# isoDebug-FTDI.net
KiCad netlist of a schematic drawn in Altium Designer
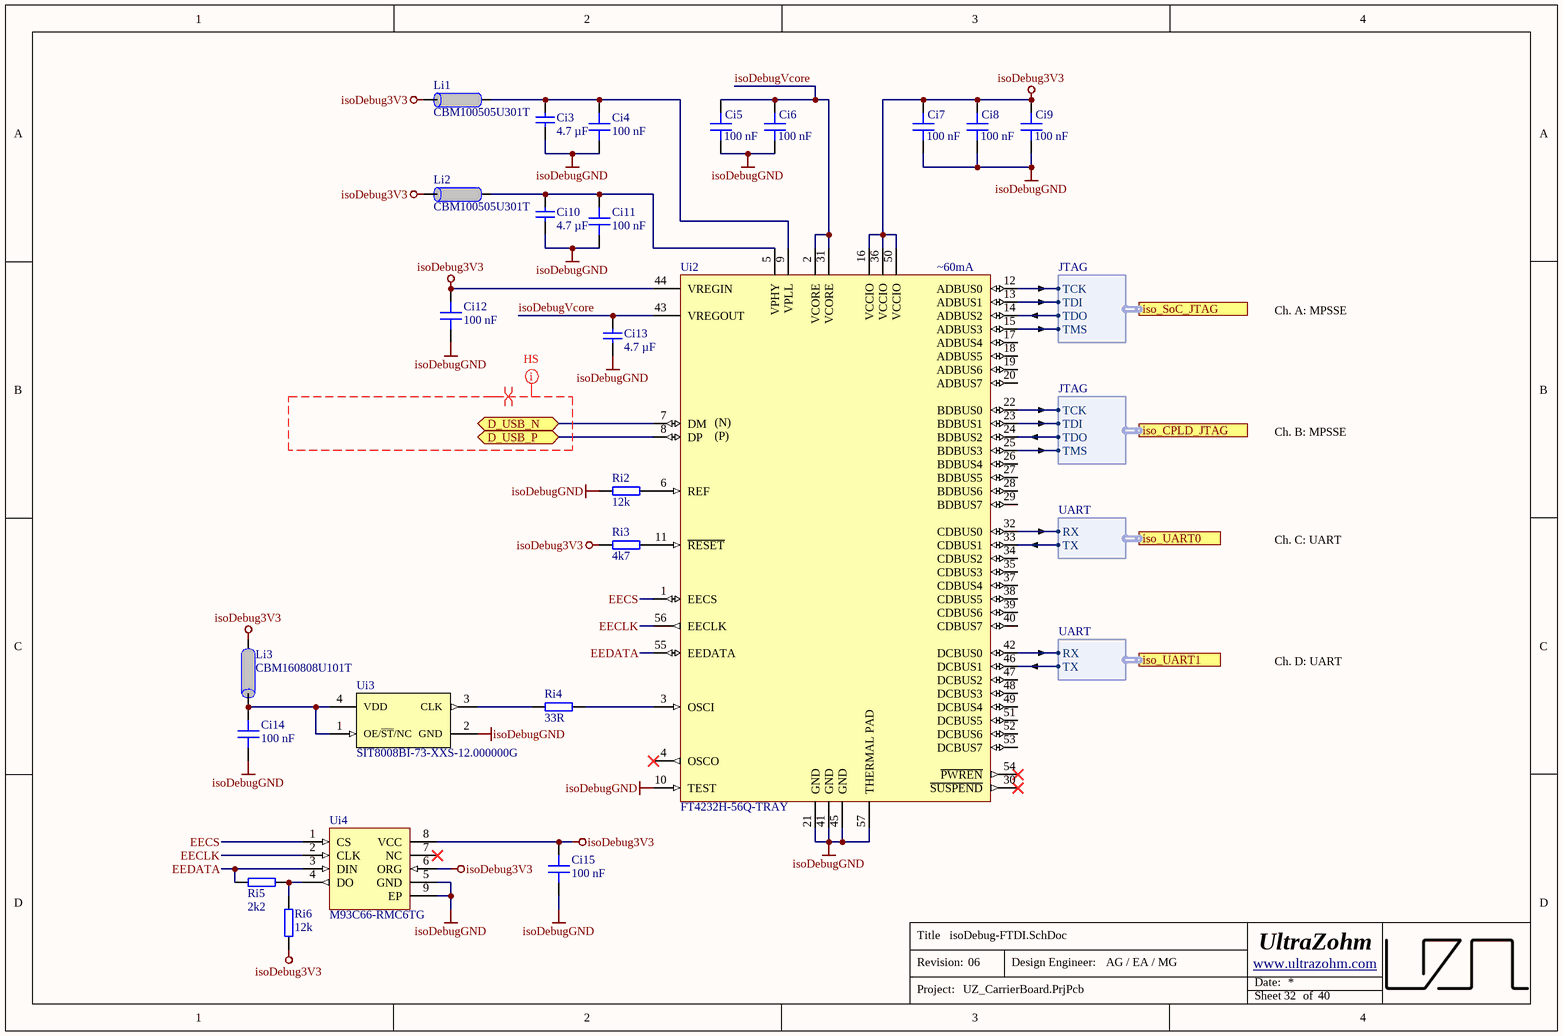
[diagram p0: isoDebug-FTDI.SchDoc]

(export (version "E")
  (design (tool "Eeschema 10.0.6"))
  (components
    (comp (ref "Ci3")
      (value "4.7 µF")
      (footprint "C_0603_TE")
      (description "Generic capacitor")
      (fields
        (field (name "MANUFACTURER PART NUMBER") "UZgen_C_0603_4.7uF_16V_X5R")
        (field (name "MANUFACTURER") "UZgen")
        (field (name "CREATED FROM") "MGeier")
      )
      (libsource (lib "user") (part "CAP-NP"))
    )
    (comp (ref "Ci4")
      (value "100 nF")
      (footprint "C_0402_TE")
      (description "50V 100nF X7R ±10% 0402 Multilayer Ceramic Capacitors MLCC - SMD/SMT ROHS")
      (fields
        (field (name "MANUFACTURER PART NUMBER") "GRM155R71H104KE14D")
        (field (name "MANUFACTURER") "Murata Electronics")
        (field (name "CREATED FROM") "AGeiger")
      )
      (libsource (lib "user") (part "Capacitor"))
    )
    (comp (ref "Ci5")
      (value "100 nF")
      (footprint "C_0402_TE")
      (description "50V 100nF X7R ±10% 0402 Multilayer Ceramic Capacitors MLCC - SMD/SMT ROHS")
      (fields
        (field (name "MANUFACTURER PART NUMBER") "GRM155R71H104KE14D")
        (field (name "MANUFACTURER") "Murata Electronics")
        (field (name "CREATED FROM") "AGeiger")
      )
      (libsource (lib "user") (part "Capacitor"))
    )
    (comp (ref "Ci6")
      (value "100 nF")
      (footprint "C_0402_TE")
      (description "50V 100nF X7R ±10% 0402 Multilayer Ceramic Capacitors MLCC - SMD/SMT ROHS")
      (fields
        (field (name "MANUFACTURER PART NUMBER") "GRM155R71H104KE14D")
        (field (name "MANUFACTURER") "Murata Electronics")
        (field (name "CREATED FROM") "AGeiger")
      )
      (libsource (lib "user") (part "Capacitor"))
    )
    (comp (ref "Ci7")
      (value "100 nF")
      (footprint "C_0402_TE")
      (description "50V 100nF X7R ±10% 0402 Multilayer Ceramic Capacitors MLCC - SMD/SMT ROHS")
      (fields
        (field (name "MANUFACTURER PART NUMBER") "GRM155R71H104KE14D")
        (field (name "MANUFACTURER") "Murata Electronics")
        (field (name "CREATED FROM") "AGeiger")
      )
      (libsource (lib "user") (part "Capacitor"))
    )
    (comp (ref "Ci8")
      (value "100 nF")
      (footprint "C_0402_TE")
      (description "50V 100nF X7R ±10% 0402 Multilayer Ceramic Capacitors MLCC - SMD/SMT ROHS")
      (fields
        (field (name "MANUFACTURER PART NUMBER") "GRM155R71H104KE14D")
        (field (name "MANUFACTURER") "Murata Electronics")
        (field (name "CREATED FROM") "AGeiger")
      )
      (libsource (lib "user") (part "Capacitor"))
    )
    (comp (ref "Ci9")
      (value "100 nF")
      (footprint "C_0402_TE")
      (description "50V 100nF X7R ±10% 0402 Multilayer Ceramic Capacitors MLCC - SMD/SMT ROHS")
      (fields
        (field (name "MANUFACTURER PART NUMBER") "GRM155R71H104KE14D")
        (field (name "MANUFACTURER") "Murata Electronics")
        (field (name "CREATED FROM") "AGeiger")
      )
      (libsource (lib "user") (part "Capacitor"))
    )
    (comp (ref "Ci10")
      (value "4.7 µF")
      (footprint "C_0603_TE")
      (description "Generic capacitor")
      (fields
        (field (name "MANUFACTURER PART NUMBER") "UZgen_C_0603_4.7uF_16V_X5R")
        (field (name "MANUFACTURER") "UZgen")
        (field (name "CREATED FROM") "MGeier")
      )
      (libsource (lib "user") (part "CAP-NP"))
    )
    (comp (ref "Ci11")
      (value "100 nF")
      (footprint "C_0402_TE")
      (description "50V 100nF X7R ±10% 0402 Multilayer Ceramic Capacitors MLCC - SMD/SMT ROHS")
      (fields
        (field (name "MANUFACTURER PART NUMBER") "GRM155R71H104KE14D")
        (field (name "MANUFACTURER") "Murata Electronics")
        (field (name "CREATED FROM") "AGeiger")
      )
      (libsource (lib "user") (part "Capacitor"))
    )
    (comp (ref "Ci12")
      (value "100 nF")
      (footprint "C_0402_TE")
      (description "50V 100nF X7R ±10% 0402 Multilayer Ceramic Capacitors MLCC - SMD/SMT ROHS")
      (fields
        (field (name "MANUFACTURER PART NUMBER") "GRM155R71H104KE14D")
        (field (name "MANUFACTURER") "Murata Electronics")
        (field (name "CREATED FROM") "AGeiger")
      )
      (libsource (lib "user") (part "Capacitor"))
    )
    (comp (ref "Ci13")
      (value "4.7 µF")
      (footprint "C_0603_TE")
      (description "Generic capacitor")
      (fields
        (field (name "MANUFACTURER PART NUMBER") "UZgen_C_0603_4.7uF_16V_X5R")
        (field (name "MANUFACTURER") "UZgen")
        (field (name "CREATED FROM") "MGeier")
      )
      (libsource (lib "user") (part "CAP-NP"))
    )
    (comp (ref "Ci14")
      (value "100 nF")
      (footprint "C_0402_TE")
      (description "50V 100nF X7R ±10% 0402 Multilayer Ceramic Capacitors MLCC - SMD/SMT ROHS")
      (fields
        (field (name "MANUFACTURER PART NUMBER") "GRM155R71H104KE14D")
        (field (name "MANUFACTURER") "Murata Electronics")
        (field (name "CREATED FROM") "AGeiger")
      )
      (libsource (lib "user") (part "Capacitor"))
    )
    (comp (ref "Ci15")
      (value "100 nF")
      (footprint "C_0402_TE")
      (description "50V 100nF X7R ±10% 0402 Multilayer Ceramic Capacitors MLCC - SMD/SMT ROHS")
      (fields
        (field (name "MANUFACTURER PART NUMBER") "GRM155R71H104KE14D")
        (field (name "MANUFACTURER") "Murata Electronics")
        (field (name "CREATED FROM") "AGeiger")
      )
      (libsource (lib "user") (part "Capacitor"))
    )
    (comp (ref "Li1")
      (value "CBM100505U301T")
      (footprint "IND_0402_TE")
      (description "300mΩ ±25% 300Ω@100MHz 0402 Ferrite Beads ROHS")
      (fields
        (field (name "MANUFACTURER") "FH (Guangdong Fenghua Advanced Tech)")
        (field (name "LCSC PART NUMBER") "C394406")
        (field (name "CREATED FROM") "AGeiger")
      )
      (libsource (lib "user") (part "Ferrite_Bead"))
    )
    (comp (ref "Li2")
      (value "CBM100505U301T")
      (footprint "IND_0402_TE")
      (description "300mΩ ±25% 300Ω@100MHz 0402 Ferrite Beads ROHS")
      (fields
        (field (name "MANUFACTURER") "FH (Guangdong Fenghua Advanced Tech)")
        (field (name "LCSC PART NUMBER") "C394406")
        (field (name "CREATED FROM") "AGeiger")
      )
      (libsource (lib "user") (part "Ferrite_Bead"))
    )
    (comp (ref "Li3")
      (value "CBM160808U101T")
      (footprint "IND_0603_TE")
      (description "60mΩ ±25% 100Ω@100MHz 0603 Ferrite Beads ROHS")
      (fields
        (field (name "MANUFACTURER") "FH (Guangdong Fenghua Advanced Tech)")
        (field (name "LCSC PART NUMBER") "C361675")
        (field (name "CREATED FROM") "AGeiger")
      )
      (libsource (lib "") (part "Ferrite_Bead_1"))
    )
    (comp (ref "Ri2")
      (value "12k")
      (footprint "R_0603_TE")
      (description "Generic resistor")
      (fields
        (field (name "MANUFACTURER PART NUMBER") "UZgen_R_0603_12k")
        (field (name "MANUFACTURER") "UZgen")
        (field (name "CREATED FROM") "UZgenTool")
      )
      (libsource (lib "user") (part "RES"))
    )
    (comp (ref "Ri3")
      (value "4k7")
      (footprint "R_0603_TE")
      (description "Generic resistor")
      (fields
        (field (name "MANUFACTURER PART NUMBER") "UZgen_R_0603_4k7")
        (field (name "MANUFACTURER") "UZgen")
        (field (name "CREATED FROM") "UZgenTool")
      )
      (libsource (lib "user") (part "RES"))
    )
    (comp (ref "Ri4")
      (value "33R")
      (footprint "R_0603_TE")
      (description "Generic resistor")
      (fields
        (field (name "MANUFACTURER PART NUMBER") "UZgen_R_0603_33R")
        (field (name "MANUFACTURER") "UZgen")
        (field (name "CREATED FROM") "UZgenTool")
      )
      (libsource (lib "user") (part "RES"))
    )
    (comp (ref "Ri5")
      (value "2k2")
      (footprint "R_0603_TE")
      (description "Generic resistor")
      (fields
        (field (name "MANUFACTURER PART NUMBER") "UZgen_R_0603_2k2")
        (field (name "MANUFACTURER") "UZgen")
        (field (name "CREATED FROM") "UZgenTool")
      )
      (libsource (lib "user") (part "RES"))
    )
    (comp (ref "Ri6")
      (value "12k")
      (footprint "R_0603_TE")
      (description "Generic resistor")
      (fields
        (field (name "MANUFACTURER PART NUMBER") "UZgen_R_0603_12k")
        (field (name "MANUFACTURER") "UZgen")
        (field (name "CREATED FROM") "UZgenTool")
      )
      (libsource (lib "user") (part "RES"))
    )
    (comp (ref "Ui2")
      (value "FT4232H-56Q-TRAY")
      (footprint "QFN50P800X800-57T610X610N")
      (description "USB Interface IC Quad 480Mbs 4 UART USB 2.0 12Mbit")
      (fields
        (field (name "MANUFACTURER") "FTDI")
        (field (name "LCSC PART NUMBER") "C1521561")
        (field (name "CREATED FROM") "AGeiger")
      )
      (libsource (lib "user") (part "FT4232H-56Q"))
    )
    (comp (ref "Ui3")
      (value "SIT8008BI-73-XXS-12.000000G")
      (footprint "2016")
      (description "Clock-Standardoszillatoren -40 to 85C, 2016, 50ppm, 2.25V-3.63V, 12MHz, ST, 250 pcs T&R 8 mm")
      (fields
        (field (name "MANUFACTURER") "SiTime")
        (field (name "LCSC PART NUMBER") "C1508636")
        (field (name "CREATED FROM") "AGeiger")
      )
      (libsource (lib "user") (part "SiT8103"))
    )
    (comp (ref "Ui4")
      (value "M93C66-RMC6TG")
      (footprint "UFDFPN8")
      (description "4Kbit MICROWIRE EE 1.8 V to 5.5 V")
      (fields
        (field (name "MANUFACTURER") "STMicroelectronics")
        (field (name "LCSC PART NUMBER") "C2061956")
        (field (name "CREATED FROM") "AGeiger")
      )
      (libsource (lib "user") (part "M93C46-MN6P"))
    )
  )
  (nets
    (net (code "3") (name "/D_USB_N") (class "Default")
      (node (ref "Ui2") (pin "7") (pinfunction "DM_7") (pintype "bidirectional"))
    )
    (net (code "4") (name "/D_USB_P") (class "Default")
      (node (ref "Ui2") (pin "8") (pinfunction "DP_8") (pintype "bidirectional"))
    )
    (net (code "5") (name "/EECLK") (class "Default")
      (node (ref "Ui2") (pin "56") (pinfunction "EECLK_56") (pintype "output"))
      (node (ref "Ui4") (pin "2") (pinfunction "CLK_2") (pintype "input"))
    )
    (net (code "6") (name "/EECS") (class "Default")
      (node (ref "Ui2") (pin "1") (pinfunction "EECS_1") (pintype "bidirectional"))
      (node (ref "Ui4") (pin "1") (pinfunction "CS_1") (pintype "input"))
    )
    (net (code "7") (name "/EEDATA") (class "Default")
      (node (ref "Ri5") (pin "1") (pinfunction "1_1") (pintype "passive"))
      (node (ref "Ui2") (pin "55") (pinfunction "EEDATA_55") (pintype "bidirectional"))
      (node (ref "Ui4") (pin "3") (pinfunction "DIN_3") (pintype "input"))
    )
    (net (code "8") (name "/isoDebugVcore") (class "Default")
      (node (ref "Ci13") (pin "2") (pinfunction "2_2") (pintype "passive"))
      (node (ref "Ci5") (pin "2") (pinfunction "2_2") (pintype "passive"))
      (node (ref "Ci6") (pin "2") (pinfunction "2_2") (pintype "passive"))
      (node (ref "Ui2") (pin "2") (pinfunction "VCORE_2") (pintype "power_in"))
      (node (ref "Ui2") (pin "31") (pinfunction "VCORE_31") (pintype "power_in"))
      (node (ref "Ui2") (pin "43") (pinfunction "VREGOUT_43") (pintype "power_in"))
    )
    (net (code "11") (name "Net-(Ui2-OSCI)") (class "Default")
      (node (ref "Ri4") (pin "2") (pinfunction "2_2") (pintype "passive"))
      (node (ref "Ui2") (pin "3") (pinfunction "OSCI_3") (pintype "input"))
    )
    (net (code "12") (name "Net-(Ui2-REF)") (class "Default")
      (node (ref "Ri2") (pin "2") (pinfunction "2_2") (pintype "passive"))
      (node (ref "Ui2") (pin "6") (pinfunction "REF_6") (pintype "input"))
    )
    (net (code "13") (name "Net-(Ui2-VPHY)") (class "Default")
      (node (ref "Ci10") (pin "2") (pinfunction "2_2") (pintype "passive"))
      (node (ref "Ci11") (pin "2") (pinfunction "2_2") (pintype "passive"))
      (node (ref "Li2") (pin "1") (pinfunction "1_1") (pintype "passive"))
      (node (ref "Ui2") (pin "5") (pinfunction "VPHY_5") (pintype "power_in"))
    )
    (net (code "14") (name "Net-(Ui2-VPLL)") (class "Default")
      (node (ref "Ci3") (pin "2") (pinfunction "2_2") (pintype "passive"))
      (node (ref "Ci4") (pin "2") (pinfunction "2_2") (pintype "passive"))
      (node (ref "Li1") (pin "1") (pinfunction "1_1") (pintype "passive"))
      (node (ref "Ui2") (pin "9") (pinfunction "VPLL_9") (pintype "power_in"))
    )
    (net (code "15") (name "Net-(Ui2-~{RESET})") (class "Default")
      (node (ref "Ri3") (pin "2") (pinfunction "2_2") (pintype "passive"))
      (node (ref "Ui2") (pin "11") (pinfunction "~{RESET}_11") (pintype "input"))
    )
    (net (code "16") (name "Net-(Ui3-CLK)") (class "Default")
      (node (ref "Ri4") (pin "1") (pinfunction "1_1") (pintype "passive"))
      (node (ref "Ui3") (pin "3") (pinfunction "CLK_3") (pintype "output"))
    )
    (net (code "17") (name "Net-(Ui3-OE{slash}~{ST}{slash}NC)") (class "Default")
      (node (ref "Ci14") (pin "2") (pinfunction "2_2") (pintype "passive"))
      (node (ref "Li3") (pin "2") (pinfunction "2_2") (pintype "passive"))
      (node (ref "Ui3") (pin "1") (pinfunction "OE/~{ST}/NC_1") (pintype "input"))
      (node (ref "Ui3") (pin "4") (pinfunction "VDD_4") (pintype "power_in"))
    )
    (net (code "18") (name "Net-(Ui4-DO)") (class "Default")
      (node (ref "Ri5") (pin "2") (pinfunction "2_2") (pintype "passive"))
      (node (ref "Ri6") (pin "2") (pinfunction "2_2") (pintype "passive"))
      (node (ref "Ui4") (pin "4") (pinfunction "DO_4") (pintype "output"))
    )
    (net (code "19") (name "isoDebug3V3") (class "Default")
      (node (ref "Ci12") (pin "2") (pinfunction "2_2") (pintype "passive"))
      (node (ref "Ci15") (pin "2") (pinfunction "2_2") (pintype "passive"))
      (node (ref "Ci7") (pin "2") (pinfunction "2_2") (pintype "passive"))
      (node (ref "Ci8") (pin "2") (pinfunction "2_2") (pintype "passive"))
      (node (ref "Ci9") (pin "2") (pinfunction "2_2") (pintype "passive"))
      (node (ref "Li1") (pin "2") (pinfunction "2_2") (pintype "passive"))
      (node (ref "Li2") (pin "2") (pinfunction "2_2") (pintype "passive"))
      (node (ref "Li3") (pin "1") (pinfunction "1_1") (pintype "passive"))
      (node (ref "Ri3") (pin "1") (pinfunction "1_1") (pintype "passive"))
      (node (ref "Ri6") (pin "1") (pinfunction "1_1") (pintype "passive"))
      (node (ref "Ui2") (pin "16") (pinfunction "VCCIO_16") (pintype "power_in"))
      (node (ref "Ui2") (pin "36") (pinfunction "VCCIO_36") (pintype "power_in"))
      (node (ref "Ui2") (pin "44") (pinfunction "VREGIN_44") (pintype "power_in"))
      (node (ref "Ui2") (pin "50") (pinfunction "VCCIO_50") (pintype "power_in"))
      (node (ref "Ui4") (pin "6") (pinfunction "ORG_6") (pintype "input"))
      (node (ref "Ui4") (pin "8") (pinfunction "VCC_8") (pintype "power_in"))
    )
    (net (code "20") (name "isoDebugGND") (class "Default")
      (node (ref "Ci10") (pin "1") (pinfunction "1_1") (pintype "passive"))
      (node (ref "Ci11") (pin "1") (pinfunction "1_1") (pintype "passive"))
      (node (ref "Ci12") (pin "1") (pinfunction "1_1") (pintype "passive"))
      (node (ref "Ci13") (pin "1") (pinfunction "1_1") (pintype "passive"))
      (node (ref "Ci14") (pin "1") (pinfunction "1_1") (pintype "passive"))
      (node (ref "Ci15") (pin "1") (pinfunction "1_1") (pintype "passive"))
      (node (ref "Ci3") (pin "1") (pinfunction "1_1") (pintype "passive"))
      (node (ref "Ci4") (pin "1") (pinfunction "1_1") (pintype "passive"))
      (node (ref "Ci5") (pin "1") (pinfunction "1_1") (pintype "passive"))
      (node (ref "Ci6") (pin "1") (pinfunction "1_1") (pintype "passive"))
      (node (ref "Ci7") (pin "1") (pinfunction "1_1") (pintype "passive"))
      (node (ref "Ci8") (pin "1") (pinfunction "1_1") (pintype "passive"))
      (node (ref "Ci9") (pin "1") (pinfunction "1_1") (pintype "passive"))
      (node (ref "Ri2") (pin "1") (pinfunction "1_1") (pintype "passive"))
      (node (ref "Ui2") (pin "10") (pinfunction "TEST_10") (pintype "input"))
      (node (ref "Ui2") (pin "21") (pinfunction "GND_21") (pintype "power_in"))
      (node (ref "Ui2") (pin "41") (pinfunction "GND_41") (pintype "power_in"))
      (node (ref "Ui2") (pin "45") (pinfunction "GND_45") (pintype "power_in"))
      (node (ref "Ui2") (pin "57") (pinfunction "THERMAL_PAD_57") (pintype "power_in"))
      (node (ref "Ui3") (pin "2") (pinfunction "GND_2") (pintype "power_in"))
      (node (ref "Ui4") (pin "5") (pinfunction "GND_5") (pintype "power_in"))
      (node (ref "Ui4") (pin "9") (pinfunction "EP_9") (pintype "power_in"))
    )
    (net (code "21") (name "unconnected-(Ui2-ADBUS0-Pad12)") (class "Default")
      (node (ref "Ui2") (pin "12") (pinfunction "ADBUS0_12") (pintype "bidirectional"))
    )
    (net (code "22") (name "unconnected-(Ui2-ADBUS1-Pad13)") (class "Default")
      (node (ref "Ui2") (pin "13") (pinfunction "ADBUS1_13") (pintype "bidirectional"))
    )
    (net (code "23") (name "unconnected-(Ui2-ADBUS2-Pad14)") (class "Default")
      (node (ref "Ui2") (pin "14") (pinfunction "ADBUS2_14") (pintype "bidirectional"))
    )
    (net (code "24") (name "unconnected-(Ui2-ADBUS3-Pad15)") (class "Default")
      (node (ref "Ui2") (pin "15") (pinfunction "ADBUS3_15") (pintype "bidirectional"))
    )
    (net (code "25") (name "unconnected-(Ui2-ADBUS4-Pad17)") (class "Default")
      (node (ref "Ui2") (pin "17") (pinfunction "ADBUS4_17") (pintype "bidirectional"))
    )
    (net (code "26") (name "unconnected-(Ui2-ADBUS5-Pad18)") (class "Default")
      (node (ref "Ui2") (pin "18") (pinfunction "ADBUS5_18") (pintype "bidirectional"))
    )
    (net (code "27") (name "unconnected-(Ui2-ADBUS6-Pad19)") (class "Default")
      (node (ref "Ui2") (pin "19") (pinfunction "ADBUS6_19") (pintype "bidirectional"))
    )
    (net (code "28") (name "unconnected-(Ui2-ADBUS7-Pad20)") (class "Default")
      (node (ref "Ui2") (pin "20") (pinfunction "ADBUS7_20") (pintype "bidirectional"))
    )
    (net (code "29") (name "unconnected-(Ui2-BDBUS0-Pad22)") (class "Default")
      (node (ref "Ui2") (pin "22") (pinfunction "BDBUS0_22") (pintype "bidirectional"))
    )
    (net (code "30") (name "unconnected-(Ui2-BDBUS1-Pad23)") (class "Default")
      (node (ref "Ui2") (pin "23") (pinfunction "BDBUS1_23") (pintype "bidirectional"))
    )
    (net (code "31") (name "unconnected-(Ui2-BDBUS2-Pad24)") (class "Default")
      (node (ref "Ui2") (pin "24") (pinfunction "BDBUS2_24") (pintype "bidirectional"))
    )
    (net (code "32") (name "unconnected-(Ui2-BDBUS3-Pad25)") (class "Default")
      (node (ref "Ui2") (pin "25") (pinfunction "BDBUS3_25") (pintype "bidirectional"))
    )
    (net (code "33") (name "unconnected-(Ui2-BDBUS4-Pad26)") (class "Default")
      (node (ref "Ui2") (pin "26") (pinfunction "BDBUS4_26") (pintype "bidirectional"))
    )
    (net (code "34") (name "unconnected-(Ui2-BDBUS5-Pad27)") (class "Default")
      (node (ref "Ui2") (pin "27") (pinfunction "BDBUS5_27") (pintype "bidirectional"))
    )
    (net (code "35") (name "unconnected-(Ui2-BDBUS6-Pad28)") (class "Default")
      (node (ref "Ui2") (pin "28") (pinfunction "BDBUS6_28") (pintype "bidirectional"))
    )
    (net (code "36") (name "unconnected-(Ui2-BDBUS7-Pad29)") (class "Default")
      (node (ref "Ui2") (pin "29") (pinfunction "BDBUS7_29") (pintype "bidirectional"))
    )
    (net (code "37") (name "unconnected-(Ui2-CDBUS0-Pad32)") (class "Default")
      (node (ref "Ui2") (pin "32") (pinfunction "CDBUS0_32") (pintype "bidirectional"))
    )
    (net (code "38") (name "unconnected-(Ui2-CDBUS1-Pad33)") (class "Default")
      (node (ref "Ui2") (pin "33") (pinfunction "CDBUS1_33") (pintype "bidirectional"))
    )
    (net (code "39") (name "unconnected-(Ui2-CDBUS2-Pad34)") (class "Default")
      (node (ref "Ui2") (pin "34") (pinfunction "CDBUS2_34") (pintype "bidirectional"))
    )
    (net (code "40") (name "unconnected-(Ui2-CDBUS3-Pad35)") (class "Default")
      (node (ref "Ui2") (pin "35") (pinfunction "CDBUS3_35") (pintype "bidirectional"))
    )
    (net (code "41") (name "unconnected-(Ui2-CDBUS4-Pad37)") (class "Default")
      (node (ref "Ui2") (pin "37") (pinfunction "CDBUS4_37") (pintype "bidirectional"))
    )
    (net (code "42") (name "unconnected-(Ui2-CDBUS5-Pad38)") (class "Default")
      (node (ref "Ui2") (pin "38") (pinfunction "CDBUS5_38") (pintype "bidirectional"))
    )
    (net (code "43") (name "unconnected-(Ui2-CDBUS6-Pad39)") (class "Default")
      (node (ref "Ui2") (pin "39") (pinfunction "CDBUS6_39") (pintype "bidirectional"))
    )
    (net (code "44") (name "unconnected-(Ui2-CDBUS7-Pad40)") (class "Default")
      (node (ref "Ui2") (pin "40") (pinfunction "CDBUS7_40") (pintype "bidirectional"))
    )
    (net (code "45") (name "unconnected-(Ui2-DCBUS0-Pad42)") (class "Default")
      (node (ref "Ui2") (pin "42") (pinfunction "DCBUS0_42") (pintype "bidirectional"))
    )
    (net (code "46") (name "unconnected-(Ui2-DCBUS1-Pad46)") (class "Default")
      (node (ref "Ui2") (pin "46") (pinfunction "DCBUS1_46") (pintype "bidirectional"))
    )
    (net (code "47") (name "unconnected-(Ui2-DCBUS2-Pad47)") (class "Default")
      (node (ref "Ui2") (pin "47") (pinfunction "DCBUS2_47") (pintype "bidirectional"))
    )
    (net (code "48") (name "unconnected-(Ui2-DCBUS3-Pad48)") (class "Default")
      (node (ref "Ui2") (pin "48") (pinfunction "DCBUS3_48") (pintype "bidirectional"))
    )
    (net (code "49") (name "unconnected-(Ui2-DCBUS4-Pad49)") (class "Default")
      (node (ref "Ui2") (pin "49") (pinfunction "DCBUS4_49") (pintype "bidirectional"))
    )
    (net (code "50") (name "unconnected-(Ui2-DCBUS5-Pad51)") (class "Default")
      (node (ref "Ui2") (pin "51") (pinfunction "DCBUS5_51") (pintype "bidirectional"))
    )
    (net (code "51") (name "unconnected-(Ui2-DCBUS6-Pad52)") (class "Default")
      (node (ref "Ui2") (pin "52") (pinfunction "DCBUS6_52") (pintype "bidirectional"))
    )
    (net (code "52") (name "unconnected-(Ui2-DCBUS7-Pad53)") (class "Default")
      (node (ref "Ui2") (pin "53") (pinfunction "DCBUS7_53") (pintype "bidirectional"))
    )
    (net (code "53") (name "unconnected-(Ui2-OSCO-Pad4)") (class "Default")
      (node (ref "Ui2") (pin "4") (pinfunction "OSCO_4") (pintype "output+no_connect"))
    )
    (net (code "54") (name "unconnected-(Ui2-~{PWREN}-Pad54)") (class "Default")
      (node (ref "Ui2") (pin "54") (pinfunction "~{PWREN}_54") (pintype "output+no_connect"))
    )
    (net (code "55") (name "unconnected-(Ui2-~{SUSPEND}-Pad30)") (class "Default")
      (node (ref "Ui2") (pin "30") (pinfunction "~{SUSPEND}_30") (pintype "output+no_connect"))
    )
    (net (code "56") (name "unconnected-(Ui4-NC-Pad7)") (class "Default")
      (node (ref "Ui4") (pin "7") (pinfunction "NC_7") (pintype "passive+no_connect"))
    )
  )
)
